# MioShield.net
KiCad netlist of a schematic drawn in Altium Designer
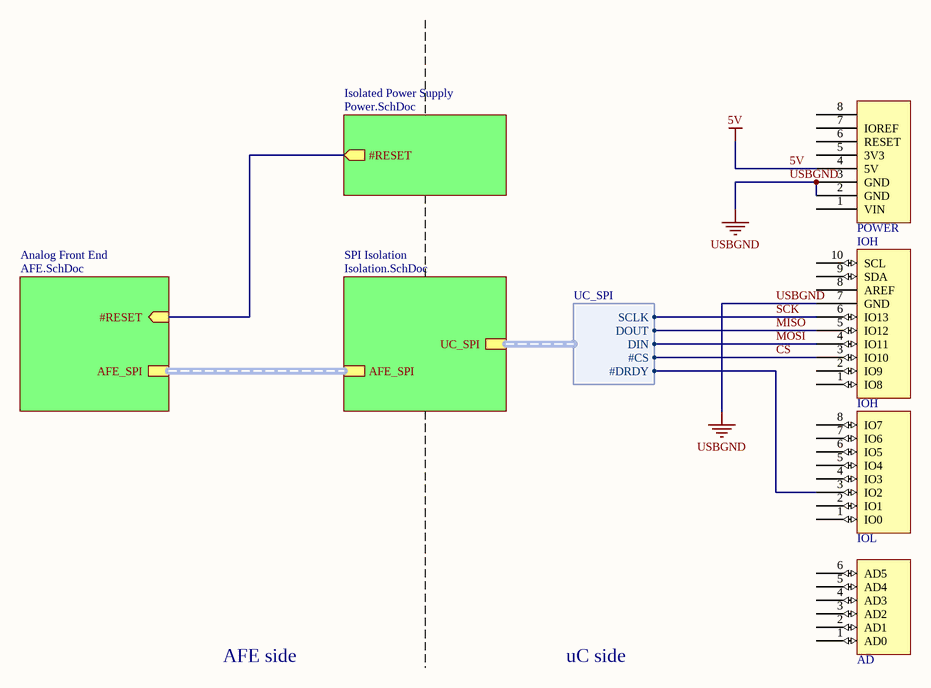
[diagram p0: MioShield.SchDoc]

(export (version "E")
  (design (tool "Eeschema 10.0.6"))
  (components
    (comp (ref "AD")
      (value "AD")
      (footprint "Header:Header 6x1 8.5mm")
      (libsource (lib "Header") (part "AD"))
    )
    (comp (ref "IOH")
      (value "IOH")
      (footprint "Header:Header 10x1 8.5mm")
      (libsource (lib "Header") (part "IOH"))
    )
    (comp (ref "IOL") (value "IOL") (footprint "Header 8x1 8.5mm") (libsource (lib "Header") (part "IOL")))
    (comp (ref "POWER")
      (value "POWER_UNO")
      (footprint "Header 8x1 8.5mm")
      (libsource (lib "Header") (part "POWER_UNO"))
    )
  )
  (nets
    (net (code "2") (name "/#DRDY") (class "Default")
      (node (ref "IOL") (pin "3") (pinfunction "IO2_3") (pintype "bidirectional"))
    )
    (net (code "5") (name "/CS") (class "Default")
      (node (ref "IOH") (pin "3") (pinfunction "IO10_3") (pintype "bidirectional"))
    )
    (net (code "6") (name "/MISO") (class "Default")
      (node (ref "IOH") (pin "5") (pinfunction "IO12_5") (pintype "bidirectional"))
    )
    (net (code "7") (name "/MOSI") (class "Default")
      (node (ref "IOH") (pin "4") (pinfunction "IO11_4") (pintype "bidirectional"))
    )
    (net (code "8") (name "/SCK") (class "Default")
      (node (ref "IOH") (pin "6") (pinfunction "IO13_6") (pintype "bidirectional"))
    )
    (net (code "10") (name "5V") (class "Default")
      (node (ref "POWER") (pin "4") (pinfunction "5V_4") (pintype "power_in"))
    )
    (net (code "11") (name "USBGND") (class "Default")
      (node (ref "IOH") (pin "7") (pinfunction "GND_7") (pintype "power_in"))
      (node (ref "POWER") (pin "2") (pinfunction "GND_2") (pintype "power_in"))
      (node (ref "POWER") (pin "3") (pinfunction "GND_3") (pintype "power_in"))
    )
    (net (code "12") (name "unconnected-(AD-AD0-Pad1)") (class "Default")
      (node (ref "AD") (pin "1") (pinfunction "AD0_1") (pintype "bidirectional"))
    )
    (net (code "13") (name "unconnected-(AD-AD1-Pad2)") (class "Default")
      (node (ref "AD") (pin "2") (pinfunction "AD1_2") (pintype "bidirectional"))
    )
    (net (code "14") (name "unconnected-(AD-AD2-Pad3)") (class "Default")
      (node (ref "AD") (pin "3") (pinfunction "AD2_3") (pintype "bidirectional"))
    )
    (net (code "15") (name "unconnected-(AD-AD3-Pad4)") (class "Default")
      (node (ref "AD") (pin "4") (pinfunction "AD3_4") (pintype "bidirectional"))
    )
    (net (code "16") (name "unconnected-(AD-AD4-Pad5)") (class "Default")
      (node (ref "AD") (pin "5") (pinfunction "AD4_5") (pintype "bidirectional"))
    )
    (net (code "17") (name "unconnected-(AD-AD5-Pad6)") (class "Default")
      (node (ref "AD") (pin "6") (pinfunction "AD5_6") (pintype "bidirectional"))
    )
    (net (code "18") (name "unconnected-(IOH-AREF-Pad8)") (class "Default")
      (node (ref "IOH") (pin "8") (pinfunction "AREF_8") (pintype "passive"))
    )
    (net (code "19") (name "unconnected-(IOH-IO8-Pad1)") (class "Default")
      (node (ref "IOH") (pin "1") (pinfunction "IO8_1") (pintype "bidirectional"))
    )
    (net (code "20") (name "unconnected-(IOH-IO9-Pad2)") (class "Default")
      (node (ref "IOH") (pin "2") (pinfunction "IO9_2") (pintype "bidirectional"))
    )
    (net (code "21") (name "unconnected-(IOH-SCL-Pad10)") (class "Default")
      (node (ref "IOH") (pin "10") (pinfunction "SCL_10") (pintype "bidirectional"))
    )
    (net (code "22") (name "unconnected-(IOH-SDA-Pad9)") (class "Default")
      (node (ref "IOH") (pin "9") (pinfunction "SDA_9") (pintype "bidirectional"))
    )
    (net (code "23") (name "unconnected-(IOL-IO0-Pad1)") (class "Default")
      (node (ref "IOL") (pin "1") (pinfunction "IO0_1") (pintype "bidirectional"))
    )
    (net (code "24") (name "unconnected-(IOL-IO1-Pad2)") (class "Default")
      (node (ref "IOL") (pin "2") (pinfunction "IO1_2") (pintype "bidirectional"))
    )
    (net (code "25") (name "unconnected-(IOL-IO3-Pad4)") (class "Default")
      (node (ref "IOL") (pin "4") (pinfunction "IO3_4") (pintype "bidirectional"))
    )
    (net (code "26") (name "unconnected-(IOL-IO4-Pad5)") (class "Default")
      (node (ref "IOL") (pin "5") (pinfunction "IO4_5") (pintype "bidirectional"))
    )
    (net (code "27") (name "unconnected-(IOL-IO5-Pad6)") (class "Default")
      (node (ref "IOL") (pin "6") (pinfunction "IO5_6") (pintype "bidirectional"))
    )
    (net (code "28") (name "unconnected-(IOL-IO6-Pad7)") (class "Default")
      (node (ref "IOL") (pin "7") (pinfunction "IO6_7") (pintype "bidirectional"))
    )
    (net (code "29") (name "unconnected-(IOL-IO7-Pad8)") (class "Default")
      (node (ref "IOL") (pin "8") (pinfunction "IO7_8") (pintype "bidirectional"))
    )
    (net (code "30") (name "unconnected-(POWER-3V3-Pad5)") (class "Default")
      (node (ref "POWER") (pin "5") (pinfunction "3V3_5") (pintype "power_in"))
    )
    (net (code "31") (name "unconnected-(POWER-IOREF-Pad7)") (class "Default")
      (node (ref "POWER") (pin "7") (pinfunction "IOREF_7") (pintype "power_in"))
    )
    (net (code "32") (name "unconnected-(POWER-Pad8)") (class "Default")
      (node (ref "POWER") (pin "8") (pintype "passive"))
    )
    (net (code "33") (name "unconnected-(POWER-RESET-Pad6)") (class "Default")
      (node (ref "POWER") (pin "6") (pinfunction "RESET_6") (pintype "passive"))
    )
    (net (code "34") (name "unconnected-(POWER-VIN-Pad1)") (class "Default")
      (node (ref "POWER") (pin "1") (pinfunction "VIN_1") (pintype "power_in"))
    )
  )
)
